# SCH_glow_cube_v2_2023-04-08.net
KiCad netlist of a schematic drawn in EasyEDA
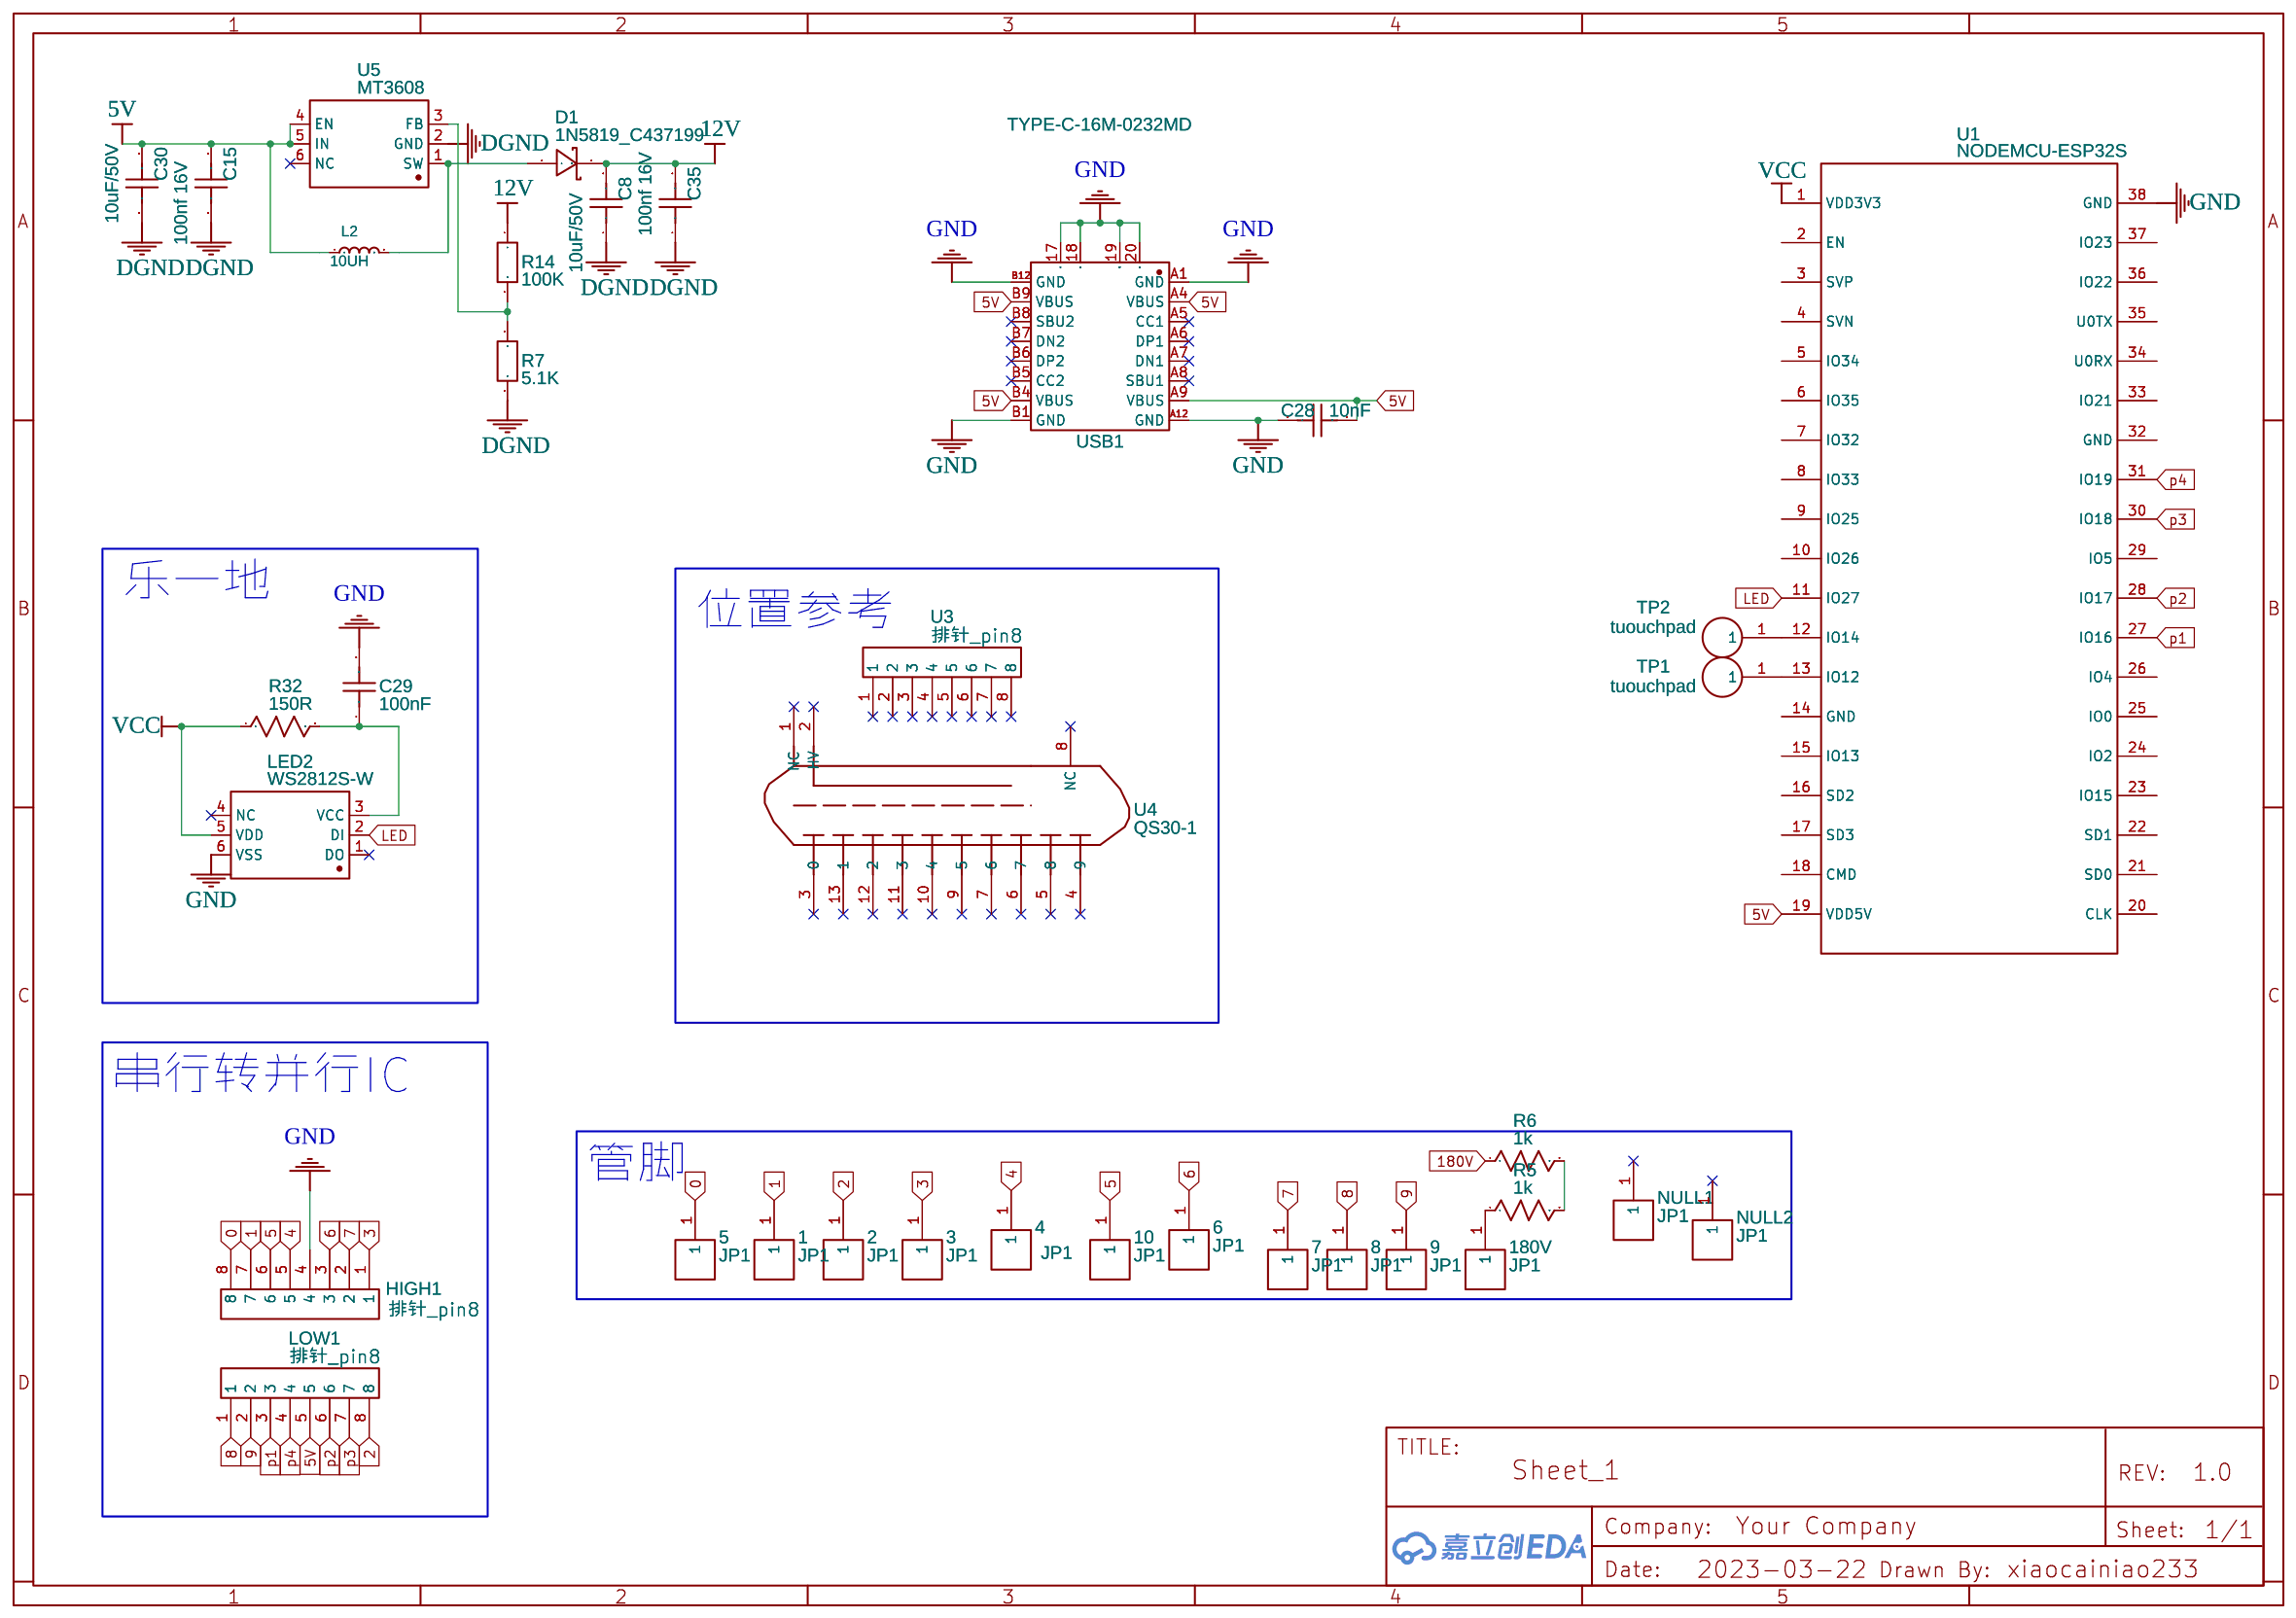
[diagram p0: schematic sheet]

(export (version "E")
  (design (tool "Eeschema 10.0.6"))
  (components
    (comp (ref "1") (value "JP1") (libsource (lib "") (part "JP1")))
    (comp (ref "2") (value "JP1") (libsource (lib "") (part "JP1")))
    (comp (ref "3") (value "JP1") (libsource (lib "") (part "JP1")))
    (comp (ref "4") (value "JP1") (libsource (lib "") (part "JP1")))
    (comp (ref "5") (value "JP1") (libsource (lib "") (part "JP1")))
    (comp (ref "6") (value "JP1") (libsource (lib "") (part "JP1")))
    (comp (ref "7") (value "JP1") (libsource (lib "") (part "JP1")))
    (comp (ref "8") (value "JP1") (libsource (lib "") (part "JP1")))
    (comp (ref "9") (value "JP1") (libsource (lib "") (part "JP1")))
    (comp (ref "10") (value "JP1") (libsource (lib "") (part "JP1")))
    (comp (ref "180V") (value "JP1") (libsource (lib "") (part "JP1_1")))
    (comp (ref "C8") (value "10uF/50V") (libsource (lib "") (part "C_0805_US")))
    (comp (ref "C15") (value "100nf 16V") (libsource (lib "") (part "C_0603_US")))
    (comp (ref "C28") (value "10nF") (libsource (lib "") (part "C_0603_US_1")))
    (comp (ref "C29") (value "100nF") (libsource (lib "") (part "C_0402_US")))
    (comp (ref "C30") (value "10uF/50V") (libsource (lib "") (part "C_0805_US")))
    (comp (ref "C35") (value "100nf 16V") (libsource (lib "") (part "C_0603_US")))
    (comp (ref "D1")
      (value "1N5819_C437199")
      (fields (field (name "BOM_Manufacturer Part") "1N5819") (field (name "BOM_Supplier Part") "C437199"))
      (libsource (lib "") (part "1N5819_C437199"))
    )
    (comp (ref "HIGH1") (value "排针_pin8") (libsource (lib "") (part "排针_pin8")))
    (comp (ref "L2") (value "10UH") (libsource (lib "") (part "Unknown_175_-685")))
    (comp (ref "LED2")
      (value "WS2812S-W")
      (fields (field (name "BOM_Manufacturer Part") "WS2812S") (field (name "BOM_Supplier Part") "C114584"))
      (libsource (lib "") (part "WS2812S-W"))
    )
    (comp (ref "LOW1") (value "排针_pin8") (libsource (lib "") (part "排针_pin8_2")))
    (comp (ref "NULL1") (value "JP1") (libsource (lib "") (part "JP1_2")))
    (comp (ref "NULL2") (value "JP1") (libsource (lib "") (part "JP1_2")))
    (comp (ref "R5") (value "1k") (libsource (lib "") (part "R_AXIAL-0.3_US")))
    (comp (ref "R6") (value "1k") (libsource (lib "") (part "R_AXIAL-0.3_US")))
    (comp (ref "R7") (value "5.1K") (libsource (lib "") (part "R_0603_EU")))
    (comp (ref "R14") (value "100K") (libsource (lib "") (part "R_0603_EU")))
    (comp (ref "R32") (value "150R") (libsource (lib "") (part "R_0603_US")))
    (comp (ref "TP1") (value "tuouchpad") (libsource (lib "") (part "tuouchpad")))
    (comp (ref "TP2") (value "tuouchpad") (libsource (lib "") (part "tuouchpad")))
    (comp (ref "U1") (value "NODEMCU-ESP32S") (libsource (lib "") (part "NODEMCU-ESP32S")))
    (comp (ref "U3") (value "排针_pin8") (libsource (lib "") (part "排针_pin8_1")))
    (comp (ref "U4") (value "QS30-1") (libsource (lib "") (part "QS30-1")))
    (comp (ref "U5")
      (value "MT3608")
      (fields (field (name "BOM_Supplier Part") "C84817"))
      (libsource (lib "") (part "MT3608"))
    )
    (comp (ref "USB1")
      (value "TYPE-C-16M-0232MD")
      (fields (field (name "BOM_Supplier Part") "C2798171"))
      (libsource (lib "") (part "TYPE-C-16M-0232MD"))
    )
  )
  (nets
    (net (code "1") (name "0") (class "Default")
      (node (ref "5") (pin "1") (pinfunction "1_1") (pintype "unspecified"))
      (node (ref "HIGH1") (pin "8") (pinfunction "8_8") (pintype "unspecified"))
    )
    (net (code "2") (name "1") (class "Default")
      (node (ref "1") (pin "1") (pinfunction "1_1") (pintype "unspecified"))
      (node (ref "HIGH1") (pin "7") (pinfunction "7_7") (pintype "unspecified"))
    )
    (net (code "3") (name "2") (class "Default")
      (node (ref "2") (pin "1") (pinfunction "1_1") (pintype "unspecified"))
      (node (ref "LOW1") (pin "8") (pinfunction "8_8") (pintype "unspecified"))
    )
    (net (code "4") (name "3") (class "Default")
      (node (ref "3") (pin "1") (pinfunction "1_1") (pintype "unspecified"))
      (node (ref "HIGH1") (pin "1") (pinfunction "1_1") (pintype "unspecified"))
    )
    (net (code "5") (name "4") (class "Default")
      (node (ref "4") (pin "1") (pinfunction "1_1") (pintype "unspecified"))
      (node (ref "HIGH1") (pin "5") (pinfunction "5_5") (pintype "unspecified"))
    )
    (net (code "6") (name "5") (class "Default")
      (node (ref "10") (pin "1") (pinfunction "1_1") (pintype "unspecified"))
      (node (ref "HIGH1") (pin "6") (pinfunction "6_6") (pintype "unspecified"))
    )
    (net (code "7") (name "5V") (class "Default")
      (node (ref "C15") (pin "2") (pinfunction "2_2") (pintype "unspecified"))
      (node (ref "C28") (pin "2") (pinfunction "2_2") (pintype "unspecified"))
      (node (ref "C30") (pin "2") (pinfunction "2_2") (pintype "unspecified"))
      (node (ref "L2") (pin "1") (pinfunction "1_1") (pintype "unspecified"))
      (node (ref "LOW1") (pin "5") (pinfunction "5_5") (pintype "unspecified"))
      (node (ref "U1") (pin "19") (pinfunction "VDD5V_19") (pintype "unspecified"))
      (node (ref "U5") (pin "4") (pinfunction "EN_4") (pintype "unspecified"))
      (node (ref "U5") (pin "5") (pinfunction "IN_5") (pintype "unspecified"))
      (node (ref "USB1") (pin "A4") (pinfunction "VBUS_A4") (pintype "unspecified"))
      (node (ref "USB1") (pin "A9") (pinfunction "VBUS_A9") (pintype "unspecified"))
      (node (ref "USB1") (pin "B4") (pinfunction "VBUS_B4") (pintype "unspecified"))
      (node (ref "USB1") (pin "B9") (pinfunction "VBUS_B9") (pintype "unspecified"))
    )
    (net (code "8") (name "6") (class "Default")
      (node (ref "6") (pin "1") (pinfunction "1_1") (pintype "unspecified"))
      (node (ref "HIGH1") (pin "3") (pinfunction "3_3") (pintype "unspecified"))
    )
    (net (code "9") (name "7") (class "Default")
      (node (ref "7") (pin "1") (pinfunction "1_1") (pintype "unspecified"))
      (node (ref "HIGH1") (pin "2") (pinfunction "2_2") (pintype "unspecified"))
    )
    (net (code "10") (name "8") (class "Default")
      (node (ref "8") (pin "1") (pinfunction "1_1") (pintype "unspecified"))
      (node (ref "LOW1") (pin "1") (pinfunction "1_1") (pintype "unspecified"))
    )
    (net (code "11") (name "9") (class "Default")
      (node (ref "9") (pin "1") (pinfunction "1_1") (pintype "unspecified"))
      (node (ref "LOW1") (pin "2") (pinfunction "2_2") (pintype "unspecified"))
    )
    (net (code "12") (name "12V") (class "Default")
      (node (ref "C35") (pin "2") (pinfunction "2_2") (pintype "unspecified"))
      (node (ref "C8") (pin "2") (pinfunction "2_2") (pintype "unspecified"))
      (node (ref "D1") (pin "1") (pinfunction "C_1") (pintype "unspecified"))
      (node (ref "R14") (pin "1") (pinfunction "1_1") (pintype "unspecified"))
    )
    (net (code "13") (name "180V") (class "Default")
      (node (ref "R6") (pin "1") (pinfunction "1_1") (pintype "unspecified"))
    )
    (net (code "14") (name "DGND") (class "Default")
      (node (ref "C15") (pin "1") (pinfunction "1_1") (pintype "unspecified"))
      (node (ref "C30") (pin "1") (pinfunction "1_1") (pintype "unspecified"))
      (node (ref "C35") (pin "1") (pinfunction "1_1") (pintype "unspecified"))
      (node (ref "C8") (pin "1") (pinfunction "1_1") (pintype "unspecified"))
      (node (ref "R7") (pin "2") (pinfunction "2_2") (pintype "unspecified"))
      (node (ref "U5") (pin "2") (pinfunction "GND_2") (pintype "unspecified"))
    )
    (net (code "15") (name "GND") (class "Default")
      (node (ref "C28") (pin "1") (pinfunction "1_1") (pintype "unspecified"))
      (node (ref "C29") (pin "2") (pinfunction "2_2") (pintype "unspecified"))
      (node (ref "HIGH1") (pin "4") (pinfunction "4_4") (pintype "unspecified"))
      (node (ref "LED2") (pin "6") (pinfunction "VSS_6") (pintype "unspecified"))
      (node (ref "U1") (pin "38") (pinfunction "GND_38") (pintype "unspecified"))
      (node (ref "USB1") (pin "17") (pinfunction "17_17") (pintype "unspecified"))
      (node (ref "USB1") (pin "18") (pinfunction "18_18") (pintype "unspecified"))
      (node (ref "USB1") (pin "19") (pinfunction "19_19") (pintype "unspecified"))
      (node (ref "USB1") (pin "20") (pinfunction "20_20") (pintype "unspecified"))
      (node (ref "USB1") (pin "A1") (pinfunction "GND_A1") (pintype "unspecified"))
      (node (ref "USB1") (pin "A12") (pinfunction "GND_A12") (pintype "unspecified"))
      (node (ref "USB1") (pin "B1") (pinfunction "GND_B1") (pintype "unspecified"))
      (node (ref "USB1") (pin "B12") (pinfunction "GND_B12") (pintype "unspecified"))
    )
    (net (code "16") (name "LED") (class "Default")
      (node (ref "LED2") (pin "2") (pinfunction "DI_2") (pintype "unspecified"))
      (node (ref "U1") (pin "11") (pinfunction "IO27_11") (pintype "unspecified"))
    )
    (net (code "17") (name "Net-(180V-Pad1)") (class "Default")
      (node (ref "180V") (pin "1") (pinfunction "1_1") (pintype "unspecified"))
      (node (ref "R5") (pin "1") (pinfunction "1_1") (pintype "unspecified"))
    )
    (net (code "18") (name "Net-(D1-A)") (class "Default")
      (node (ref "D1") (pin "2") (pinfunction "A_2") (pintype "unspecified"))
      (node (ref "L2") (pin "2") (pinfunction "2_2") (pintype "unspecified"))
      (node (ref "U5") (pin "1") (pinfunction "SW_1") (pintype "unspecified"))
    )
    (net (code "19") (name "Net-(LED2-VCC)") (class "Default")
      (node (ref "C29") (pin "1") (pinfunction "1_1") (pintype "unspecified"))
      (node (ref "LED2") (pin "3") (pinfunction "VCC_3") (pintype "unspecified"))
      (node (ref "R32") (pin "2") (pinfunction "2_2") (pintype "unspecified"))
    )
    (net (code "20") (name "Net-(R5-Pad2)") (class "Default")
      (node (ref "R5") (pin "2") (pinfunction "2_2") (pintype "unspecified"))
      (node (ref "R6") (pin "2") (pinfunction "2_2") (pintype "unspecified"))
    )
    (net (code "21") (name "Net-(U1-IO12)") (class "Default")
      (node (ref "TP1") (pin "1") (pinfunction "1_1") (pintype "unspecified"))
      (node (ref "U1") (pin "13") (pinfunction "IO12_13") (pintype "unspecified"))
    )
    (net (code "22") (name "Net-(U1-IO14)") (class "Default")
      (node (ref "TP2") (pin "1") (pinfunction "1_1") (pintype "unspecified"))
      (node (ref "U1") (pin "12") (pinfunction "IO14_12") (pintype "unspecified"))
    )
    (net (code "23") (name "Net-(U5-FB)") (class "Default")
      (node (ref "R14") (pin "2") (pinfunction "2_2") (pintype "unspecified"))
      (node (ref "R7") (pin "1") (pinfunction "1_1") (pintype "unspecified"))
      (node (ref "U5") (pin "3") (pinfunction "FB_3") (pintype "unspecified"))
    )
    (net (code "24") (name "VCC") (class "Default")
      (node (ref "LED2") (pin "5") (pinfunction "VDD_5") (pintype "unspecified"))
      (node (ref "R32") (pin "1") (pinfunction "1_1") (pintype "unspecified"))
      (node (ref "U1") (pin "1") (pinfunction "VDD3V3_1") (pintype "unspecified"))
    )
    (net (code "25") (name "p1") (class "Default")
      (node (ref "LOW1") (pin "3") (pinfunction "3_3") (pintype "unspecified"))
      (node (ref "U1") (pin "27") (pinfunction "IO16_27") (pintype "unspecified"))
    )
    (net (code "26") (name "p2") (class "Default")
      (node (ref "LOW1") (pin "6") (pinfunction "6_6") (pintype "unspecified"))
      (node (ref "U1") (pin "28") (pinfunction "IO17_28") (pintype "unspecified"))
    )
    (net (code "27") (name "p3") (class "Default")
      (node (ref "LOW1") (pin "7") (pinfunction "7_7") (pintype "unspecified"))
      (node (ref "U1") (pin "30") (pinfunction "IO18_30") (pintype "unspecified"))
    )
    (net (code "28") (name "p4") (class "Default")
      (node (ref "LOW1") (pin "4") (pinfunction "4_4") (pintype "unspecified"))
      (node (ref "U1") (pin "31") (pinfunction "IO19_31") (pintype "unspecified"))
    )
    (net (code "29") (name "unconnected-(LED2-DO-Pad1)") (class "Default")
      (node (ref "LED2") (pin "1") (pinfunction "DO_1") (pintype "unspecified+no_connect"))
    )
    (net (code "30") (name "unconnected-(LED2-NC-Pad4)") (class "Default")
      (node (ref "LED2") (pin "4") (pinfunction "NC_4") (pintype "unspecified+no_connect"))
    )
    (net (code "31") (name "unconnected-(NULL1-Pad1)") (class "Default")
      (node (ref "NULL1") (pin "1") (pinfunction "1_1") (pintype "unspecified+no_connect"))
    )
    (net (code "32") (name "unconnected-(NULL2-Pad1)") (class "Default")
      (node (ref "NULL2") (pin "1") (pinfunction "1_1") (pintype "unspecified+no_connect"))
    )
    (net (code "33") (name "unconnected-(U1-CLK-Pad20)") (class "Default")
      (node (ref "U1") (pin "20") (pinfunction "CLK_20") (pintype "unspecified"))
    )
    (net (code "34") (name "unconnected-(U1-CMD-Pad18)") (class "Default")
      (node (ref "U1") (pin "18") (pinfunction "CMD_18") (pintype "unspecified"))
    )
    (net (code "35") (name "unconnected-(U1-EN-Pad2)") (class "Default")
      (node (ref "U1") (pin "2") (pinfunction "EN_2") (pintype "unspecified"))
    )
    (net (code "36") (name "unconnected-(U1-GND-Pad14)") (class "Default")
      (node (ref "U1") (pin "14") (pinfunction "GND_14") (pintype "unspecified"))
    )
    (net (code "37") (name "unconnected-(U1-GND-Pad32)") (class "Default")
      (node (ref "U1") (pin "32") (pinfunction "GND_32") (pintype "unspecified"))
    )
    (net (code "38") (name "unconnected-(U1-IO0-Pad25)") (class "Default")
      (node (ref "U1") (pin "25") (pinfunction "IO0_25") (pintype "unspecified"))
    )
    (net (code "39") (name "unconnected-(U1-IO2-Pad24)") (class "Default")
      (node (ref "U1") (pin "24") (pinfunction "IO2_24") (pintype "unspecified"))
    )
    (net (code "40") (name "unconnected-(U1-IO4-Pad26)") (class "Default")
      (node (ref "U1") (pin "26") (pinfunction "IO4_26") (pintype "unspecified"))
    )
    (net (code "41") (name "unconnected-(U1-IO5-Pad29)") (class "Default")
      (node (ref "U1") (pin "29") (pinfunction "IO5_29") (pintype "unspecified"))
    )
    (net (code "42") (name "unconnected-(U1-IO13-Pad15)") (class "Default")
      (node (ref "U1") (pin "15") (pinfunction "IO13_15") (pintype "unspecified"))
    )
    (net (code "43") (name "unconnected-(U1-IO15-Pad23)") (class "Default")
      (node (ref "U1") (pin "23") (pinfunction "IO15_23") (pintype "unspecified"))
    )
    (net (code "44") (name "unconnected-(U1-IO21-Pad33)") (class "Default")
      (node (ref "U1") (pin "33") (pinfunction "IO21_33") (pintype "unspecified"))
    )
    (net (code "45") (name "unconnected-(U1-IO22-Pad36)") (class "Default")
      (node (ref "U1") (pin "36") (pinfunction "IO22_36") (pintype "unspecified"))
    )
    (net (code "46") (name "unconnected-(U1-IO23-Pad37)") (class "Default")
      (node (ref "U1") (pin "37") (pinfunction "IO23_37") (pintype "unspecified"))
    )
    (net (code "47") (name "unconnected-(U1-IO25-Pad9)") (class "Default")
      (node (ref "U1") (pin "9") (pinfunction "IO25_9") (pintype "unspecified"))
    )
    (net (code "48") (name "unconnected-(U1-IO26-Pad10)") (class "Default")
      (node (ref "U1") (pin "10") (pinfunction "IO26_10") (pintype "unspecified"))
    )
    (net (code "49") (name "unconnected-(U1-IO32-Pad7)") (class "Default")
      (node (ref "U1") (pin "7") (pinfunction "IO32_7") (pintype "unspecified"))
    )
    (net (code "50") (name "unconnected-(U1-IO33-Pad8)") (class "Default")
      (node (ref "U1") (pin "8") (pinfunction "IO33_8") (pintype "unspecified"))
    )
    (net (code "51") (name "unconnected-(U1-IO34-Pad5)") (class "Default")
      (node (ref "U1") (pin "5") (pinfunction "IO34_5") (pintype "unspecified"))
    )
    (net (code "52") (name "unconnected-(U1-IO35-Pad6)") (class "Default")
      (node (ref "U1") (pin "6") (pinfunction "IO35_6") (pintype "unspecified"))
    )
    (net (code "53") (name "unconnected-(U1-SD0-Pad21)") (class "Default")
      (node (ref "U1") (pin "21") (pinfunction "SD0_21") (pintype "unspecified"))
    )
    (net (code "54") (name "unconnected-(U1-SD1-Pad22)") (class "Default")
      (node (ref "U1") (pin "22") (pinfunction "SD1_22") (pintype "unspecified"))
    )
    (net (code "55") (name "unconnected-(U1-SD2-Pad16)") (class "Default")
      (node (ref "U1") (pin "16") (pinfunction "SD2_16") (pintype "unspecified"))
    )
    (net (code "56") (name "unconnected-(U1-SD3-Pad17)") (class "Default")
      (node (ref "U1") (pin "17") (pinfunction "SD3_17") (pintype "unspecified"))
    )
    (net (code "57") (name "unconnected-(U1-SVN-Pad4)") (class "Default")
      (node (ref "U1") (pin "4") (pinfunction "SVN_4") (pintype "unspecified"))
    )
    (net (code "58") (name "unconnected-(U1-SVP-Pad3)") (class "Default")
      (node (ref "U1") (pin "3") (pinfunction "SVP_3") (pintype "unspecified"))
    )
    (net (code "59") (name "unconnected-(U1-U0RX-Pad34)") (class "Default")
      (node (ref "U1") (pin "34") (pinfunction "U0RX_34") (pintype "unspecified"))
    )
    (net (code "60") (name "unconnected-(U1-U0TX-Pad35)") (class "Default")
      (node (ref "U1") (pin "35") (pinfunction "U0TX_35") (pintype "unspecified"))
    )
    (net (code "61") (name "unconnected-(U3-Pad1)") (class "Default")
      (node (ref "U3") (pin "1") (pinfunction "1_1") (pintype "unspecified+no_connect"))
    )
    (net (code "62") (name "unconnected-(U3-Pad2)") (class "Default")
      (node (ref "U3") (pin "2") (pinfunction "2_2") (pintype "unspecified+no_connect"))
    )
    (net (code "63") (name "unconnected-(U3-Pad3)") (class "Default")
      (node (ref "U3") (pin "3") (pinfunction "3_3") (pintype "unspecified+no_connect"))
    )
    (net (code "64") (name "unconnected-(U3-Pad4)") (class "Default")
      (node (ref "U3") (pin "4") (pinfunction "4_4") (pintype "unspecified+no_connect"))
    )
    (net (code "65") (name "unconnected-(U3-Pad5)") (class "Default")
      (node (ref "U3") (pin "5") (pinfunction "5_5") (pintype "unspecified+no_connect"))
    )
    (net (code "66") (name "unconnected-(U3-Pad6)") (class "Default")
      (node (ref "U3") (pin "6") (pinfunction "6_6") (pintype "unspecified+no_connect"))
    )
    (net (code "67") (name "unconnected-(U3-Pad7)") (class "Default")
      (node (ref "U3") (pin "7") (pinfunction "7_7") (pintype "unspecified+no_connect"))
    )
    (net (code "68") (name "unconnected-(U3-Pad8)") (class "Default")
      (node (ref "U3") (pin "8") (pinfunction "8_8") (pintype "unspecified+no_connect"))
    )
    (net (code "69") (name "unconnected-(U4-0-Pad3)") (class "Default")
      (node (ref "U4") (pin "3") (pinfunction "0_3") (pintype "unspecified+no_connect"))
    )
    (net (code "70") (name "unconnected-(U4-1-Pad13)") (class "Default")
      (node (ref "U4") (pin "13") (pinfunction "1_13") (pintype "unspecified+no_connect"))
    )
    (net (code "71") (name "unconnected-(U4-2-Pad12)") (class "Default")
      (node (ref "U4") (pin "12") (pinfunction "2_12") (pintype "unspecified+no_connect"))
    )
    (net (code "72") (name "unconnected-(U4-3-Pad11)") (class "Default")
      (node (ref "U4") (pin "11") (pinfunction "3_11") (pintype "unspecified+no_connect"))
    )
    (net (code "73") (name "unconnected-(U4-4-Pad10)") (class "Default")
      (node (ref "U4") (pin "10") (pinfunction "4_10") (pintype "unspecified+no_connect"))
    )
    (net (code "74") (name "unconnected-(U4-5-Pad9)") (class "Default")
      (node (ref "U4") (pin "9") (pinfunction "5_9") (pintype "unspecified+no_connect"))
    )
    (net (code "75") (name "unconnected-(U4-6-Pad7)") (class "Default")
      (node (ref "U4") (pin "7") (pinfunction "6_7") (pintype "unspecified+no_connect"))
    )
    (net (code "76") (name "unconnected-(U4-7-Pad6)") (class "Default")
      (node (ref "U4") (pin "6") (pinfunction "7_6") (pintype "unspecified+no_connect"))
    )
    (net (code "77") (name "unconnected-(U4-8-Pad5)") (class "Default")
      (node (ref "U4") (pin "5") (pinfunction "8_5") (pintype "unspecified+no_connect"))
    )
    (net (code "78") (name "unconnected-(U4-9-Pad4)") (class "Default")
      (node (ref "U4") (pin "4") (pinfunction "9_4") (pintype "unspecified+no_connect"))
    )
    (net (code "79") (name "unconnected-(U4-HV-Pad2)") (class "Default")
      (node (ref "U4") (pin "2") (pinfunction "HV_2") (pintype "unspecified+no_connect"))
    )
    (net (code "80") (name "unconnected-(U4-NC-Pad1)") (class "Default")
      (node (ref "U4") (pin "1") (pinfunction "NC_1") (pintype "unspecified+no_connect"))
    )
    (net (code "81") (name "unconnected-(U4-NC-Pad8)") (class "Default")
      (node (ref "U4") (pin "8") (pinfunction "NC_8") (pintype "unspecified+no_connect"))
    )
    (net (code "82") (name "unconnected-(U5-NC-Pad6)") (class "Default")
      (node (ref "U5") (pin "6") (pinfunction "NC_6") (pintype "unspecified+no_connect"))
    )
    (net (code "83") (name "unconnected-(USB1-CC1-PadA5)") (class "Default")
      (node (ref "USB1") (pin "A5") (pinfunction "CC1_A5") (pintype "unspecified+no_connect"))
    )
    (net (code "84") (name "unconnected-(USB1-CC2-PadB5)") (class "Default")
      (node (ref "USB1") (pin "B5") (pinfunction "CC2_B5") (pintype "unspecified+no_connect"))
    )
    (net (code "85") (name "unconnected-(USB1-DN1-PadA7)") (class "Default")
      (node (ref "USB1") (pin "A7") (pinfunction "DN1_A7") (pintype "unspecified+no_connect"))
    )
    (net (code "86") (name "unconnected-(USB1-DN2-PadB7)") (class "Default")
      (node (ref "USB1") (pin "B7") (pinfunction "DN2_B7") (pintype "unspecified+no_connect"))
    )
    (net (code "87") (name "unconnected-(USB1-DP1-PadA6)") (class "Default")
      (node (ref "USB1") (pin "A6") (pinfunction "DP1_A6") (pintype "unspecified+no_connect"))
    )
    (net (code "88") (name "unconnected-(USB1-DP2-PadB6)") (class "Default")
      (node (ref "USB1") (pin "B6") (pinfunction "DP2_B6") (pintype "unspecified+no_connect"))
    )
    (net (code "89") (name "unconnected-(USB1-SBU1-PadA8)") (class "Default")
      (node (ref "USB1") (pin "A8") (pinfunction "SBU1_A8") (pintype "unspecified+no_connect"))
    )
    (net (code "90") (name "unconnected-(USB1-SBU2-PadB8)") (class "Default")
      (node (ref "USB1") (pin "B8") (pinfunction "SBU2_B8") (pintype "unspecified+no_connect"))
    )
  )
)
